# attinier85-motherboard-pth-mk-3_0.net
KiCad netlist of a schematic drawn in EAGLE
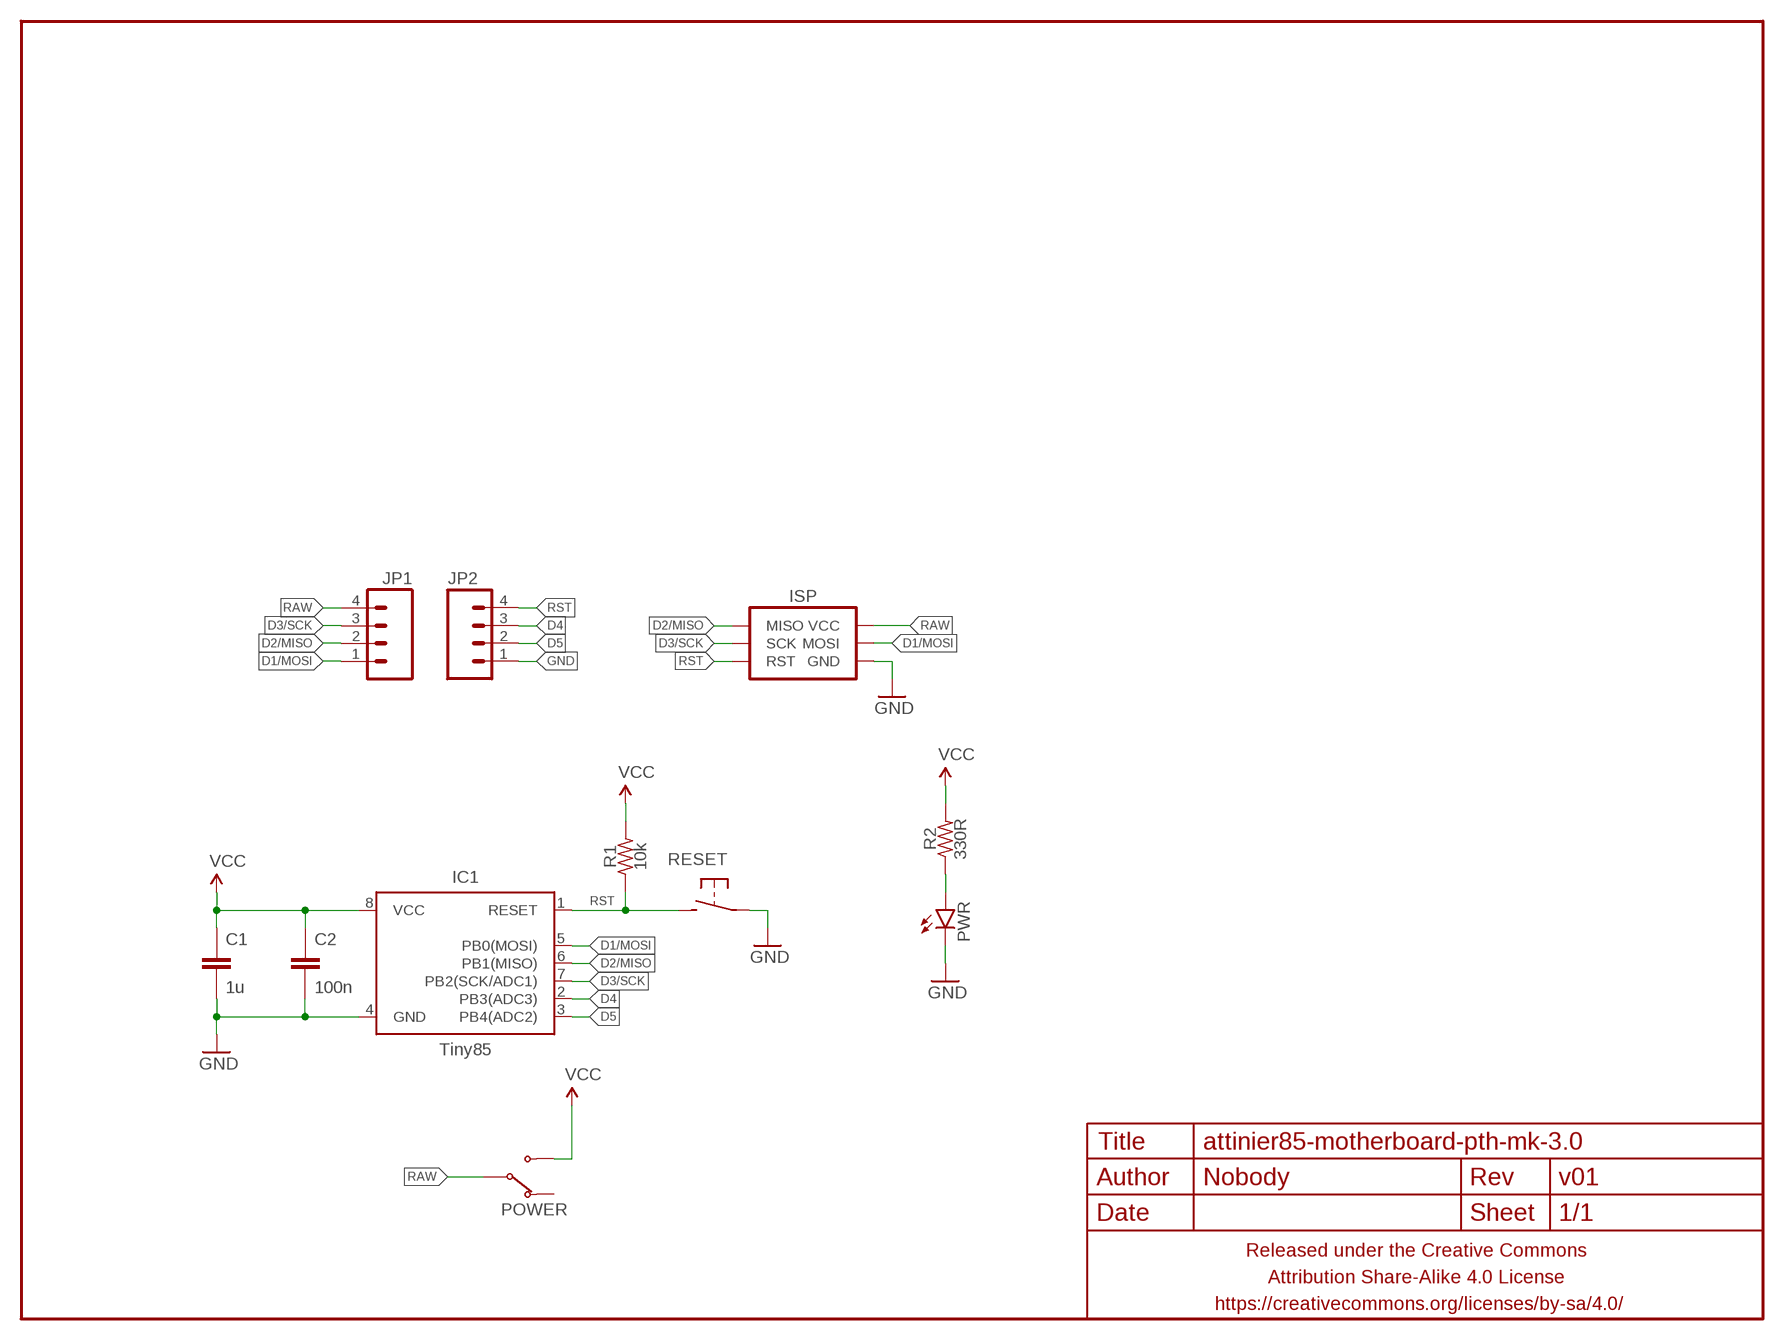
[diagram p0: schematic, sheet 1]

(export (version "E")
  (design (tool "Eeschema 10.0.6"))
  (components
    (comp (ref "C1")
      (value "1u")
      (footprint "eagle-import:C0603")
      (libsource (lib "eagle-import") (part "CAPACITOR-CERAMICC0603"))
    )
    (comp (ref "C2")
      (value "100n")
      (footprint "eagle-import:C0603")
      (libsource (lib "eagle-import") (part "CAPACITOR-CERAMICC0603"))
    )
    (comp (ref "FRAME1")
      (value "FRAME-LETTERNO_PACKAGE")
      (footprint "eagle-import:DUMMY")
      (fields (field (name "DESIGNER") "Nobody"))
      (libsource (lib "eagle-import") (part "FRAME-LETTERNO_PACKAGE"))
    )
    (comp (ref "IC1")
      (value "Tiny85")
      (footprint "eagle-import:SO08-EIAJ")
      (libsource (lib "eagle-import") (part "ATTINY45TINY85-20-SOICW"))
    )
    (comp (ref "ISP")
      (value "AVR_SPI_PRG_62X3_SMD")
      (footprint "eagle-import:2X3_SMD")
      (libsource (lib "eagle-import") (part "AVR_SPI_PRG_62X3_SMD"))
    )
    (comp (ref "JP1")
      (value "M04PTH")
      (footprint "eagle-import:1X04-PTH-VERT")
      (libsource (lib "eagle-import") (part "M04PTH"))
    )
    (comp (ref "JP2")
      (value "M04PTH")
      (footprint "eagle-import:1X04-PTH-VERT")
      (libsource (lib "eagle-import") (part "M04PTH"))
    )
    (comp (ref "POWER")
      (value "SWITCH-SPDTSMD-RA")
      (footprint "eagle-import:SWITCH-SPDT-SMD-RA")
      (libsource (lib "eagle-import") (part "SWITCH-SPDTSMD-RA"))
    )
    (comp (ref "PWR")
      (value "LED0603")
      (footprint "eagle-import:LED-0603")
      (libsource (lib "eagle-import") (part "LED0603"))
    )
    (comp (ref "R1")
      (value "10k")
      (footprint "eagle-import:R0603")
      (libsource (lib "eagle-import") (part "RESISTORR0603"))
    )
    (comp (ref "R2")
      (value "330R")
      (footprint "eagle-import:R0603")
      (libsource (lib "eagle-import") (part "RESISTORR0603"))
    )
    (comp (ref "RESET")
      (value "DTS-6MM")
      (footprint "eagle-import:B3U-1000P")
      (libsource (lib "eagle-import") (part "SPST-NO-TACTB3U-1000P"))
    )
  )
  (nets
    (net (code "1") (name "D1{slash}MOSI") (class "Default")
      (node (ref "IC1") (pin "5") (pinfunction "PB0(MOSI)_5") (pintype "bidirectional"))
      (node (ref "ISP") (pin "4") (pinfunction "MOSI_4") (pintype "passive"))
      (node (ref "JP1") (pin "1") (pinfunction "1_1") (pintype "passive"))
    )
    (net (code "2") (name "D2{slash}MISO") (class "Default")
      (node (ref "IC1") (pin "6") (pinfunction "PB1(MISO)_6") (pintype "bidirectional"))
      (node (ref "ISP") (pin "1") (pinfunction "MISO_1") (pintype "passive"))
      (node (ref "JP1") (pin "2") (pinfunction "2_2") (pintype "passive"))
    )
    (net (code "3") (name "D3{slash}SCK") (class "Default")
      (node (ref "IC1") (pin "7") (pinfunction "PB2(SCK/ADC1)_7") (pintype "bidirectional"))
      (node (ref "ISP") (pin "3") (pinfunction "SCK_3") (pintype "passive"))
      (node (ref "JP1") (pin "3") (pinfunction "3_3") (pintype "passive"))
    )
    (net (code "4") (name "D4") (class "Default")
      (node (ref "IC1") (pin "2") (pinfunction "PB3(ADC3)_2") (pintype "bidirectional"))
      (node (ref "JP2") (pin "3") (pinfunction "3_3") (pintype "passive"))
    )
    (net (code "5") (name "D5") (class "Default")
      (node (ref "IC1") (pin "3") (pinfunction "PB4(ADC2)_3") (pintype "bidirectional"))
      (node (ref "JP2") (pin "2") (pinfunction "2_2") (pintype "passive"))
    )
    (net (code "6") (name "GND") (class "Default")
      (node (ref "C1") (pin "2") (pinfunction "2_2") (pintype "passive"))
      (node (ref "C2") (pin "2") (pinfunction "2_2") (pintype "passive"))
      (node (ref "IC1") (pin "4") (pinfunction "GND_4") (pintype "bidirectional"))
      (node (ref "ISP") (pin "6") (pinfunction "GND_6") (pintype "passive"))
      (node (ref "JP2") (pin "1") (pinfunction "1_1") (pintype "passive"))
      (node (ref "PWR") (pin "C") (pinfunction "C_C") (pintype "passive"))
      (node (ref "RESET") (pin "0") (pinfunction "1_0") (pintype "passive"))
    )
    (net (code "7") (name "Net-(PWR-PadA)") (class "Default")
      (node (ref "PWR") (pin "A") (pinfunction "A_A") (pintype "passive"))
      (node (ref "R2") (pin "1") (pinfunction "1_1") (pintype "passive"))
    )
    (net (code "8") (name "RAW") (class "Default")
      (node (ref "ISP") (pin "2") (pinfunction "VCC_2") (pintype "passive"))
      (node (ref "JP1") (pin "4") (pinfunction "4_4") (pintype "passive"))
      (node (ref "POWER") (pin "2") (pinfunction "COM_2") (pintype "passive"))
    )
    (net (code "9") (name "RST") (class "Default")
      (node (ref "IC1") (pin "1") (pinfunction "RESET_1") (pintype "bidirectional"))
      (node (ref "ISP") (pin "5") (pinfunction "RST_5") (pintype "passive"))
      (node (ref "JP2") (pin "4") (pinfunction "4_4") (pintype "passive"))
      (node (ref "R1") (pin "1") (pinfunction "1_1") (pintype "passive"))
      (node (ref "RESET") (pin "1") (pinfunction "2_1") (pintype "passive"))
    )
    (net (code "10") (name "VCC") (class "Default")
      (node (ref "C1") (pin "1") (pinfunction "1_1") (pintype "passive"))
      (node (ref "C2") (pin "1") (pinfunction "1_1") (pintype "passive"))
      (node (ref "IC1") (pin "8") (pinfunction "VCC_8") (pintype "bidirectional"))
      (node (ref "POWER") (pin "1") (pinfunction "NO_1") (pintype "passive"))
      (node (ref "R1") (pin "2") (pinfunction "2_2") (pintype "passive"))
      (node (ref "R2") (pin "2") (pinfunction "2_2") (pintype "passive"))
    )
    (net (code "11") (name "unconnected-(POWER-NC-Pad3)") (class "Default")
      (node (ref "POWER") (pin "3") (pinfunction "NC_3") (pintype "passive"))
    )
  )
)
